# 1_Controller.net
KiCad netlist of a schematic drawn in Altium Designer
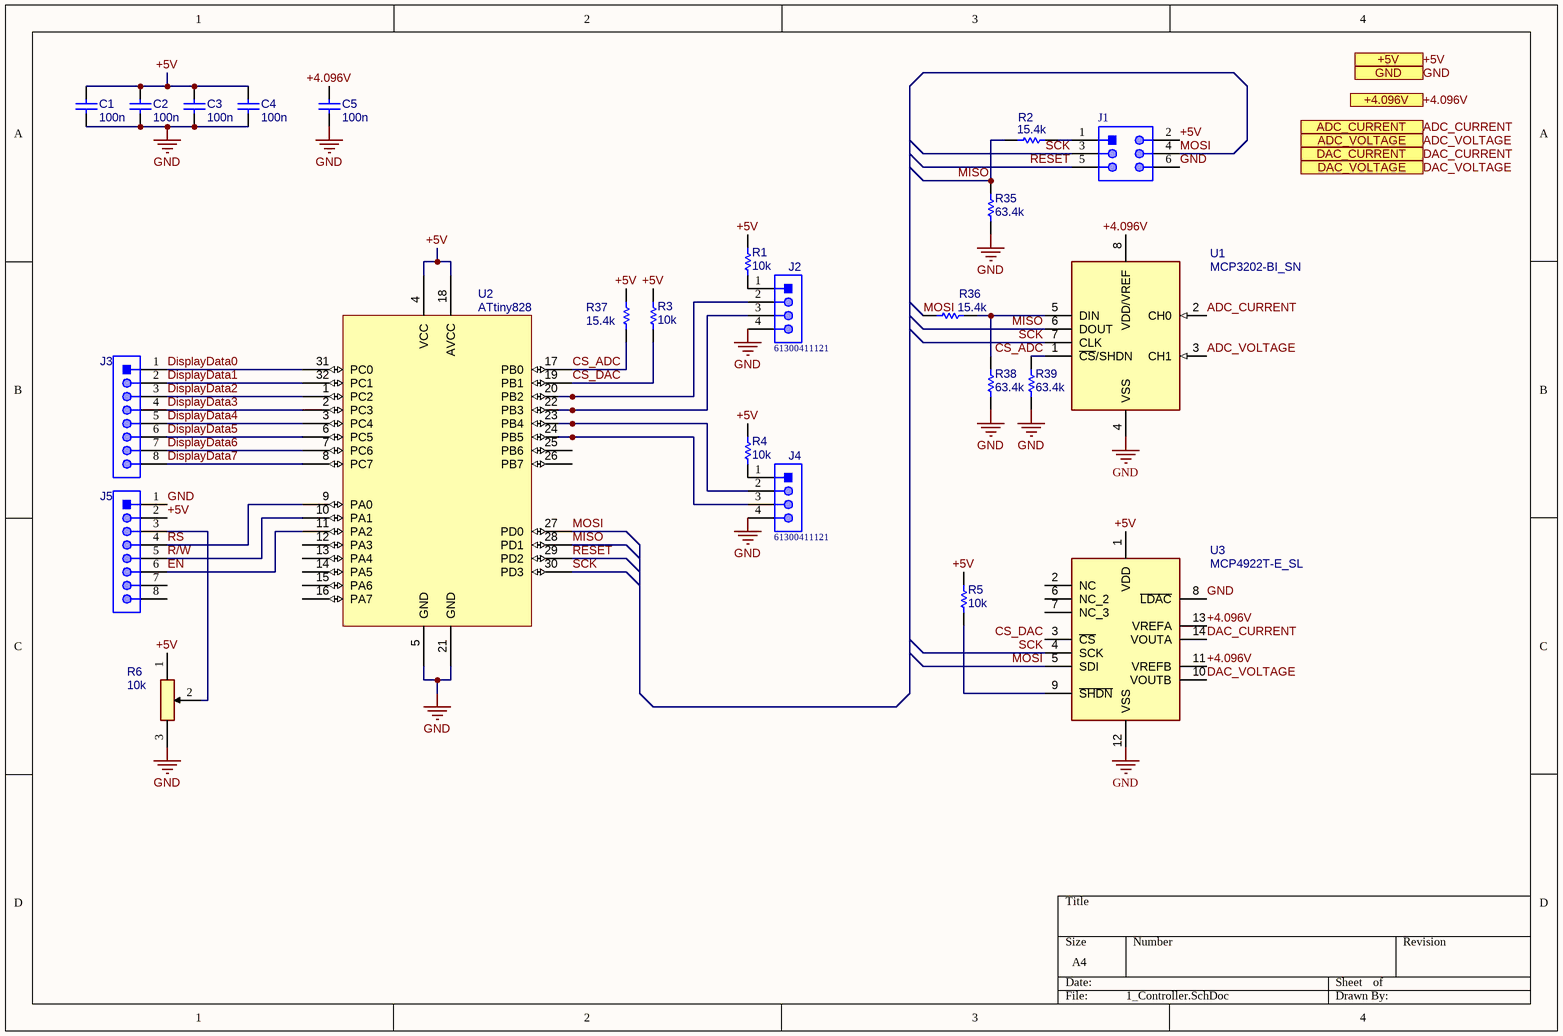
[diagram p0: 1_Controller.SchDoc]

(export (version "E")
  (design (tool "Eeschema 10.0.6"))
  (components
    (comp (ref "C1")
      (value "100n")
      (footprint "6-0805_N")
      (description "Capacitor")
      (libsource (lib "Simulation Generic Components") (part "Capacitor"))
    )
    (comp (ref "C2")
      (value "100n")
      (footprint "6-0805_N")
      (description "Capacitor")
      (libsource (lib "Simulation Generic Components") (part "Capacitor"))
    )
    (comp (ref "C3")
      (value "100n")
      (footprint "6-0805_N")
      (description "Capacitor")
      (libsource (lib "Simulation Generic Components") (part "Capacitor"))
    )
    (comp (ref "C4")
      (value "100n")
      (footprint "6-0805_N")
      (description "Capacitor")
      (libsource (lib "Simulation Generic Components") (part "Capacitor"))
    )
    (comp (ref "C5")
      (value "100n")
      (footprint "6-0805_N")
      (description "Capacitor")
      (libsource (lib "Simulation Generic Components") (part "Capacitor"))
    )
    (comp (ref "J1")
      (value "61300621121")
      (footprint "61300621121")
      (description "THT Vertical Pin Header WR-PHD, Pitch 2.54 mm, Dual Row, 6 pins")
      (fields (field (name "MANUFACTURER") "Wurth Elektronik") (field (name "PUBLISHER") "WurthElektronik"))
      (libsource (lib "Altium Content Vault") (part "WE-CN-2P-M-R6"))
    )
    (comp (ref "J2")
      (value "61300411121")
      (footprint "61300411121")
      (description "THT Vertical Pin Header WR-PHD, Pitch 2.54 mm, Single Row, 4 pins")
      (fields (field (name "MANUFACTURER") "Wurth Elektronik") (field (name "PUBLISHER") "WurthElektronik"))
      (libsource (lib "Altium Content Vault") (part "WE-CN-1P-M-R4"))
    )
    (comp (ref "J3")
      (value "61300811121")
      (footprint "61300811121")
      (description "THT Vertical Pin Header WR-PHD, Pitch 2.54 mm, Single Row, 8 pins")
      (fields (field (name "MANUFACTURER") "Wurth Elektronik") (field (name "PUBLISHER") "WurthElektronik"))
      (libsource (lib "Altium Content Vault") (part "WE-CN-1P-M-R8"))
    )
    (comp (ref "J4")
      (value "61300411121")
      (footprint "61300411121")
      (description "THT Vertical Pin Header WR-PHD, Pitch 2.54 mm, Single Row, 4 pins")
      (fields (field (name "MANUFACTURER") "Wurth Elektronik") (field (name "PUBLISHER") "WurthElektronik"))
      (libsource (lib "Altium Content Vault") (part "WE-CN-1P-M-R4"))
    )
    (comp (ref "J5")
      (value "61300811121")
      (footprint "61300811121")
      (description "THT Vertical Pin Header WR-PHD, Pitch 2.54 mm, Single Row, 8 pins")
      (fields (field (name "MANUFACTURER") "Wurth Elektronik") (field (name "PUBLISHER") "WurthElektronik"))
      (libsource (lib "Altium Content Vault") (part "WE-CN-1P-M-R8"))
    )
    (comp (ref "R1")
      (value "10k")
      (footprint "6-0805_N")
      (description "Resistor")
      (libsource (lib "Simulation Generic Components") (part "Resistor"))
    )
    (comp (ref "R2")
      (value "15.4k")
      (footprint "6-0805_N")
      (description "Resistor")
      (libsource (lib "Simulation Generic Components") (part "Resistor"))
    )
    (comp (ref "R3")
      (value "10k")
      (footprint "6-0805_N")
      (description "Resistor")
      (libsource (lib "Simulation Generic Components") (part "Resistor"))
    )
    (comp (ref "R4")
      (value "10k")
      (footprint "6-0805_N")
      (description "Resistor")
      (libsource (lib "Simulation Generic Components") (part "Resistor"))
    )
    (comp (ref "R5")
      (value "10k")
      (footprint "6-0805_N")
      (description "Resistor")
      (libsource (lib "Simulation Generic Components") (part "Resistor"))
    )
    (comp (ref "R6")
      (value "10k")
      (footprint "PV36W201C01B00")
      (description "Variable Resistor")
      (fields
        (field (name "MANUFACTURER_PART_NUMBER") "PV36W104C01B00")
        (field (name "MOUSER PART NUMBER") "81-PV36W104C01B00")
      )
      (libsource (lib "PowerSupplyPE") (part "PV36W104C01B00"))
    )
    (comp (ref "R35")
      (value "63.4k")
      (footprint "6-0805_N")
      (description "Resistor")
      (libsource (lib "Simulation Generic Components") (part "Resistor"))
    )
    (comp (ref "R36")
      (value "15.4k")
      (footprint "6-0805_N")
      (description "Resistor")
      (libsource (lib "Simulation Generic Components") (part "Resistor"))
    )
    (comp (ref "R37")
      (value "15.4k")
      (footprint "6-0805_N")
      (description "Resistor")
      (libsource (lib "Simulation Generic Components") (part "Resistor"))
    )
    (comp (ref "R38")
      (value "63.4k")
      (footprint "6-0805_N")
      (description "Resistor")
      (libsource (lib "Simulation Generic Components") (part "Resistor"))
    )
    (comp (ref "R39")
      (value "63.4k")
      (footprint "6-0805_N")
      (description "Resistor")
      (libsource (lib "Simulation Generic Components") (part "Resistor"))
    )
    (comp (ref "U1")
      (value "MCP3202-BI_SN")
      (footprint "SOIC127P600X175-8N")
      (description "Integrated Circuit")
      (fields
        (field (name "MANUFACTURER_PART_NUMBER") "MCP3202-BI/SN")
        (field (name "MOUSER PART NUMBER") "579-MCP3202BISN")
      )
      (libsource (lib "PowerSupplyPE") (part "MCP3202-BI_SN"))
    )
    (comp (ref "U2")
      (value "ATtiny828")
      (footprint "QFP80P900X900X120-32N")
      (description "Microchip ATtiny828 AVR MCU")
      (libsource (lib "PowerSupplyPE") (part "ATtiny828"))
    )
    (comp (ref "U3")
      (value "MCP4922T-E_SL")
      (footprint "SOIC127P600X175-14N")
      (description "Undefined or Miscellaneous")
      (fields
        (field (name "MANUFACTURER_PART_NUMBER") "MCP4922T-E/SL")
        (field (name "MOUSER PART NUMBER") "579-MCP4922T-E/SL")
      )
      (libsource (lib "PowerSupplyPE") (part "MCP4922T-E_SL"))
    )
  )
  (nets
    (net (code "1") (name "/+4.096V") (class "Default")
      (node (ref "C5") (pin "2") (pinfunction "2_2") (pintype "passive"))
      (node (ref "U1") (pin "8") (pinfunction "VDD/VREF_8") (pintype "power_in"))
      (node (ref "U3") (pin "11") (pinfunction "VREFB_11") (pintype "passive"))
      (node (ref "U3") (pin "13") (pinfunction "VREFA_13") (pintype "passive"))
    )
    (net (code "2") (name "/+5V") (class "Default")
      (node (ref "C1") (pin "2") (pinfunction "2_2") (pintype "passive"))
      (node (ref "C2") (pin "2") (pinfunction "2_2") (pintype "passive"))
      (node (ref "C3") (pin "2") (pinfunction "2_2") (pintype "passive"))
      (node (ref "C4") (pin "2") (pinfunction "2_2") (pintype "passive"))
      (node (ref "J1") (pin "2") (pinfunction "2_2") (pintype "passive"))
      (node (ref "J5") (pin "2") (pinfunction "2_2") (pintype "passive"))
      (node (ref "R1") (pin "2") (pinfunction "2_2") (pintype "passive"))
      (node (ref "R3") (pin "2") (pinfunction "2_2") (pintype "passive"))
      (node (ref "R37") (pin "1") (pinfunction "1_1") (pintype "passive"))
      (node (ref "R4") (pin "2") (pinfunction "2_2") (pintype "passive"))
      (node (ref "R5") (pin "2") (pinfunction "2_2") (pintype "passive"))
      (node (ref "R6") (pin "1") (pinfunction "CCW_1") (pintype "passive"))
      (node (ref "U2") (pin "18") (pinfunction "AVCC_18") (pintype "power_in"))
      (node (ref "U2") (pin "4") (pinfunction "VCC_4") (pintype "power_in"))
      (node (ref "U3") (pin "1") (pinfunction "VDD_1") (pintype "power_in"))
    )
    (net (code "3") (name "/ADC_CURRENT") (class "Default")
      (node (ref "U1") (pin "2") (pinfunction "CH0_2") (pintype "input"))
    )
    (net (code "4") (name "/ADC_VOLTAGE") (class "Default")
      (node (ref "U1") (pin "3") (pinfunction "CH1_3") (pintype "input"))
    )
    (net (code "5") (name "/CS_ADC") (class "Default")
      (node (ref "R37") (pin "2") (pinfunction "2_2") (pintype "passive"))
      (node (ref "R39") (pin "2") (pinfunction "2_2") (pintype "passive"))
      (node (ref "U1") (pin "1") (pinfunction "~{CS}/SHDN_1") (pintype "passive"))
      (node (ref "U2") (pin "17") (pinfunction "PB0_17") (pintype "bidirectional"))
    )
    (net (code "6") (name "/CS_DAC") (class "Default")
      (node (ref "R3") (pin "1") (pinfunction "1_1") (pintype "passive"))
      (node (ref "U2") (pin "19") (pinfunction "PB1_19") (pintype "bidirectional"))
      (node (ref "U3") (pin "3") (pinfunction "~{CS}_3") (pintype "passive"))
    )
    (net (code "7") (name "/DAC_CURRENT") (class "Default")
      (node (ref "U3") (pin "14") (pinfunction "VOUTA_14") (pintype "passive"))
    )
    (net (code "8") (name "/DAC_VOLTAGE") (class "Default")
      (node (ref "U3") (pin "10") (pinfunction "VOUTB_10") (pintype "passive"))
    )
    (net (code "9") (name "/DisplayData0") (class "Default")
      (node (ref "J3") (pin "1") (pinfunction "1_1") (pintype "passive"))
      (node (ref "U2") (pin "31") (pinfunction "PC0_31") (pintype "bidirectional"))
    )
    (net (code "10") (name "/DisplayData1") (class "Default")
      (node (ref "J3") (pin "2") (pinfunction "2_2") (pintype "passive"))
      (node (ref "U2") (pin "32") (pinfunction "PC1_32") (pintype "bidirectional"))
    )
    (net (code "11") (name "/DisplayData2") (class "Default")
      (node (ref "J3") (pin "3") (pinfunction "3_3") (pintype "passive"))
      (node (ref "U2") (pin "1") (pinfunction "PC2_1") (pintype "bidirectional"))
    )
    (net (code "12") (name "/DisplayData3") (class "Default")
      (node (ref "J3") (pin "4") (pinfunction "4_4") (pintype "passive"))
      (node (ref "U2") (pin "2") (pinfunction "PC3_2") (pintype "bidirectional"))
    )
    (net (code "13") (name "/DisplayData4") (class "Default")
      (node (ref "J3") (pin "5") (pinfunction "5_5") (pintype "passive"))
      (node (ref "U2") (pin "3") (pinfunction "PC4_3") (pintype "bidirectional"))
    )
    (net (code "14") (name "/DisplayData5") (class "Default")
      (node (ref "J3") (pin "6") (pinfunction "6_6") (pintype "passive"))
      (node (ref "U2") (pin "6") (pinfunction "PC5_6") (pintype "bidirectional"))
    )
    (net (code "15") (name "/DisplayData6") (class "Default")
      (node (ref "J3") (pin "7") (pinfunction "7_7") (pintype "passive"))
      (node (ref "U2") (pin "7") (pinfunction "PC6_7") (pintype "bidirectional"))
    )
    (net (code "16") (name "/DisplayData7") (class "Default")
      (node (ref "J3") (pin "8") (pinfunction "8_8") (pintype "passive"))
      (node (ref "U2") (pin "8") (pinfunction "PC7_8") (pintype "bidirectional"))
    )
    (net (code "17") (name "/EN") (class "Default")
      (node (ref "J5") (pin "6") (pinfunction "6_6") (pintype "passive"))
      (node (ref "U2") (pin "11") (pinfunction "PA2_11") (pintype "bidirectional"))
    )
    (net (code "18") (name "/MISO") (class "Default")
      (node (ref "R2") (pin "2") (pinfunction "2_2") (pintype "passive"))
      (node (ref "R35") (pin "2") (pinfunction "2_2") (pintype "passive"))
      (node (ref "U1") (pin "6") (pinfunction "DOUT_6") (pintype "passive"))
      (node (ref "U2") (pin "28") (pinfunction "PD1_28") (pintype "bidirectional"))
    )
    (net (code "19") (name "/MOSI") (class "Default")
      (node (ref "J1") (pin "4") (pinfunction "4_4") (pintype "passive"))
      (node (ref "R36") (pin "2") (pinfunction "2_2") (pintype "passive"))
      (node (ref "U2") (pin "27") (pinfunction "PD0_27") (pintype "bidirectional"))
      (node (ref "U3") (pin "5") (pinfunction "SDI_5") (pintype "passive"))
    )
    (net (code "20") (name "/RESET") (class "Default")
      (node (ref "J1") (pin "5") (pinfunction "5_5") (pintype "passive"))
      (node (ref "U2") (pin "29") (pinfunction "PD2_29") (pintype "bidirectional"))
    )
    (net (code "21") (name "/RS") (class "Default")
      (node (ref "J5") (pin "4") (pinfunction "4_4") (pintype "passive"))
      (node (ref "U2") (pin "9") (pinfunction "PA0_9") (pintype "bidirectional"))
    )
    (net (code "22") (name "/R{slash}W") (class "Default")
      (node (ref "J5") (pin "5") (pinfunction "5_5") (pintype "passive"))
      (node (ref "U2") (pin "10") (pinfunction "PA1_10") (pintype "bidirectional"))
    )
    (net (code "23") (name "/SCK") (class "Default")
      (node (ref "J1") (pin "3") (pinfunction "3_3") (pintype "passive"))
      (node (ref "U1") (pin "7") (pinfunction "CLK_7") (pintype "passive"))
      (node (ref "U2") (pin "30") (pinfunction "PD3_30") (pintype "bidirectional"))
      (node (ref "U3") (pin "4") (pinfunction "SCK_4") (pintype "passive"))
    )
    (net (code "24") (name "GND") (class "Default")
      (node (ref "C1") (pin "1") (pinfunction "1_1") (pintype "passive"))
      (node (ref "C2") (pin "1") (pinfunction "1_1") (pintype "passive"))
      (node (ref "C3") (pin "1") (pinfunction "1_1") (pintype "passive"))
      (node (ref "C4") (pin "1") (pinfunction "1_1") (pintype "passive"))
      (node (ref "C5") (pin "1") (pinfunction "1_1") (pintype "passive"))
      (node (ref "J1") (pin "6") (pinfunction "6_6") (pintype "passive"))
      (node (ref "J2") (pin "4") (pinfunction "4_4") (pintype "passive"))
      (node (ref "J4") (pin "4") (pinfunction "4_4") (pintype "passive"))
      (node (ref "J5") (pin "1") (pinfunction "1_1") (pintype "passive"))
      (node (ref "R35") (pin "1") (pinfunction "1_1") (pintype "passive"))
      (node (ref "R38") (pin "1") (pinfunction "1_1") (pintype "passive"))
      (node (ref "R39") (pin "1") (pinfunction "1_1") (pintype "passive"))
      (node (ref "R6") (pin "3") (pinfunction "CW_3") (pintype "passive"))
      (node (ref "U1") (pin "4") (pinfunction "VSS_4") (pintype "power_in"))
      (node (ref "U2") (pin "21") (pinfunction "GND_21") (pintype "power_in"))
      (node (ref "U2") (pin "5") (pinfunction "GND_5") (pintype "power_in"))
      (node (ref "U3") (pin "12") (pinfunction "VSS_12") (pintype "passive"))
      (node (ref "U3") (pin "8") (pinfunction "~{LDAC}_8") (pintype "passive"))
    )
    (net (code "25") (name "Net-(J1-Pad1)") (class "Default")
      (node (ref "J1") (pin "1") (pinfunction "1_1") (pintype "passive"))
      (node (ref "R2") (pin "1") (pinfunction "1_1") (pintype "passive"))
    )
    (net (code "26") (name "Net-(J2-Pad1)") (class "Default")
      (node (ref "J2") (pin "1") (pinfunction "1_1") (pintype "passive"))
      (node (ref "R1") (pin "1") (pinfunction "1_1") (pintype "passive"))
    )
    (net (code "27") (name "Net-(J4-Pad1)") (class "Default")
      (node (ref "J4") (pin "1") (pinfunction "1_1") (pintype "passive"))
      (node (ref "R4") (pin "1") (pinfunction "1_1") (pintype "passive"))
    )
    (net (code "28") (name "Net-(R6-WIPER)") (class "Default")
      (node (ref "J5") (pin "3") (pinfunction "3_3") (pintype "passive"))
      (node (ref "R6") (pin "2") (pinfunction "WIPER_2") (pintype "passive"))
    )
    (net (code "29") (name "Net-(U1-DIN)") (class "Default")
      (node (ref "R36") (pin "1") (pinfunction "1_1") (pintype "passive"))
      (node (ref "R38") (pin "2") (pinfunction "2_2") (pintype "passive"))
      (node (ref "U1") (pin "5") (pinfunction "DIN_5") (pintype "passive"))
    )
    (net (code "30") (name "Net-(U2-PB2)") (class "Default")
      (node (ref "J2") (pin "2") (pinfunction "2_2") (pintype "passive"))
      (node (ref "U2") (pin "20") (pinfunction "PB2_20") (pintype "bidirectional"))
    )
    (net (code "31") (name "Net-(U2-PB3)") (class "Default")
      (node (ref "J2") (pin "3") (pinfunction "3_3") (pintype "passive"))
      (node (ref "U2") (pin "22") (pinfunction "PB3_22") (pintype "bidirectional"))
    )
    (net (code "32") (name "Net-(U2-PB4)") (class "Default")
      (node (ref "J4") (pin "2") (pinfunction "2_2") (pintype "passive"))
      (node (ref "U2") (pin "23") (pinfunction "PB4_23") (pintype "bidirectional"))
    )
    (net (code "33") (name "Net-(U2-PB5)") (class "Default")
      (node (ref "J4") (pin "3") (pinfunction "3_3") (pintype "passive"))
      (node (ref "U2") (pin "24") (pinfunction "PB5_24") (pintype "bidirectional"))
    )
    (net (code "34") (name "Net-(U3-~{SHDN})") (class "Default")
      (node (ref "R5") (pin "1") (pinfunction "1_1") (pintype "passive"))
      (node (ref "U3") (pin "9") (pinfunction "~{SHDN}_9") (pintype "passive"))
    )
    (net (code "35") (name "unconnected-(J5-Pad7)") (class "Default")
      (node (ref "J5") (pin "7") (pinfunction "7_7") (pintype "passive"))
    )
    (net (code "36") (name "unconnected-(J5-Pad8)") (class "Default")
      (node (ref "J5") (pin "8") (pinfunction "8_8") (pintype "passive"))
    )
    (net (code "37") (name "unconnected-(U2-PA3-Pad12)") (class "Default")
      (node (ref "U2") (pin "12") (pinfunction "PA3_12") (pintype "bidirectional"))
    )
    (net (code "38") (name "unconnected-(U2-PA4-Pad13)") (class "Default")
      (node (ref "U2") (pin "13") (pinfunction "PA4_13") (pintype "bidirectional"))
    )
    (net (code "39") (name "unconnected-(U2-PA5-Pad14)") (class "Default")
      (node (ref "U2") (pin "14") (pinfunction "PA5_14") (pintype "bidirectional"))
    )
    (net (code "40") (name "unconnected-(U2-PA6-Pad15)") (class "Default")
      (node (ref "U2") (pin "15") (pinfunction "PA6_15") (pintype "bidirectional"))
    )
    (net (code "41") (name "unconnected-(U2-PA7-Pad16)") (class "Default")
      (node (ref "U2") (pin "16") (pinfunction "PA7_16") (pintype "bidirectional"))
    )
    (net (code "42") (name "unconnected-(U2-PB6-Pad25)") (class "Default")
      (node (ref "U2") (pin "25") (pinfunction "PB6_25") (pintype "bidirectional"))
    )
    (net (code "43") (name "unconnected-(U2-PB7-Pad26)") (class "Default")
      (node (ref "U2") (pin "26") (pinfunction "PB7_26") (pintype "bidirectional"))
    )
    (net (code "44") (name "unconnected-(U3-NC-Pad2)") (class "Default")
      (node (ref "U3") (pin "2") (pinfunction "NC_2") (pintype "passive"))
    )
    (net (code "45") (name "unconnected-(U3-NC_2-Pad6)") (class "Default")
      (node (ref "U3") (pin "6") (pinfunction "NC_2_6") (pintype "passive"))
    )
    (net (code "46") (name "unconnected-(U3-NC_3-Pad7)") (class "Default")
      (node (ref "U3") (pin "7") (pinfunction "NC_3_7") (pintype "passive"))
    )
  )
)
